# SOT23-3.net
KiCad netlist of a schematic drawn in EAGLE
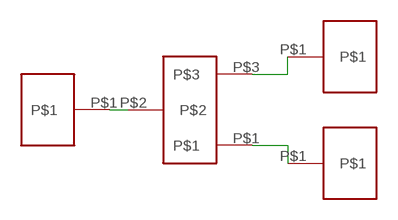
[diagram p0: schematic, sheet 1]

(export (version "E")
  (design (tool "Eeschema 10.0.6"))
  (components
    (comp (ref "U$1")
      (value "SOT23-3")
      (footprint "eagle-import:SOT23-3")
      (libsource (lib "eagle-import") (part "SOT23-3"))
    )
    (comp (ref "U$2")
      (value "PAD")
      (footprint "eagle-import:100MIL_PAD")
      (libsource (lib "eagle-import") (part "PAD"))
    )
    (comp (ref "U$3")
      (value "PAD")
      (footprint "eagle-import:100MIL_PAD")
      (libsource (lib "eagle-import") (part "PAD"))
    )
    (comp (ref "U$4")
      (value "PAD")
      (footprint "eagle-import:100MIL_PAD")
      (libsource (lib "eagle-import") (part "PAD"))
    )
  )
  (nets
    (net (code "1") (name "Net-(U$1-PadP$1)") (class "Default")
      (node (ref "U$1") (pin "P$1") (pinfunction "P$1_P$1") (pintype "bidirectional"))
      (node (ref "U$4") (pin "P$1") (pinfunction "P$1_P$1") (pintype "bidirectional"))
    )
    (net (code "2") (name "Net-(U$1-PadP$2)") (class "Default")
      (node (ref "U$1") (pin "P$2") (pinfunction "P$2_P$2") (pintype "bidirectional"))
      (node (ref "U$2") (pin "P$1") (pinfunction "P$1_P$1") (pintype "bidirectional"))
    )
    (net (code "3") (name "Net-(U$1-PadP$3)") (class "Default")
      (node (ref "U$1") (pin "P$3") (pinfunction "P$3_P$3") (pintype "bidirectional"))
      (node (ref "U$3") (pin "P$1") (pinfunction "P$1_P$1") (pintype "bidirectional"))
    )
  )
)
